# ALU.net
KiCad netlist of a schematic drawn in EAGLE
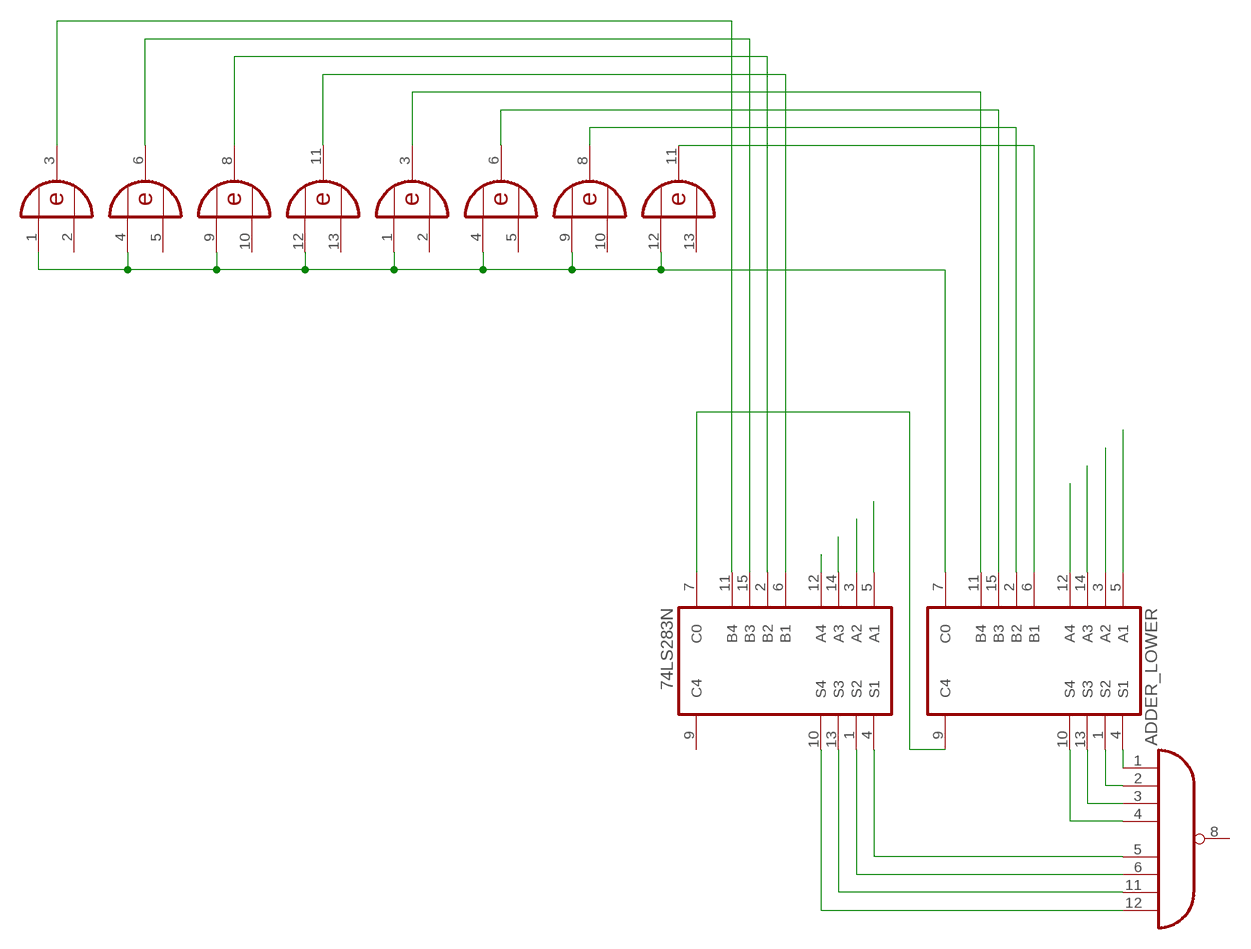
[diagram p0: schematic, sheet 1]

(export (version "E")
  (design (tool "Eeschema 10.0.6"))
  (components
    (comp (ref "ADDER_LOWER")
      (value "74LS283N")
      (footprint "eagle-import:DIL16")
      (libsource (lib "eagle-import") (part "74283NLS"))
    )
    (comp (ref "ADDER_UPPER")
      (value "74LS283N")
      (footprint "eagle-import:DIL16")
      (libsource (lib "eagle-import") (part "74283NLS"))
    )
    (comp (ref "AND_GATE1")
      (value "74LS30N")
      (footprint "eagle-import:DIL14")
      (libsource (lib "eagle-import") (part "7430NLS"))
    )
    (comp (ref "SUBTRACT_INVERTER_LOWER")
      (value "74LS86N")
      (footprint "eagle-import:DIL14")
      (libsource (lib "eagle-import") (part "7486NLS"))
    )
    (comp (ref "SUBTRACT_INVERTER_UPPER")
      (value "74LS86N")
      (footprint "eagle-import:DIL14")
      (libsource (lib "eagle-import") (part "7486NLS"))
    )
  )
  (nets
    (net (code "1") (name "Net-(ADDER_LOWERA-B1)") (class "Default")
      (node (ref "ADDER_LOWER") (pin "6") (pinfunction "B1_6") (pintype "input"))
      (node (ref "SUBTRACT_INVERTER_LOWER") (pin "11") (pinfunction "O_11") (pintype "output"))
    )
    (net (code "2") (name "Net-(ADDER_LOWERA-B2)") (class "Default")
      (node (ref "ADDER_LOWER") (pin "2") (pinfunction "B2_2") (pintype "input"))
      (node (ref "SUBTRACT_INVERTER_LOWER") (pin "8") (pinfunction "O_8") (pintype "output"))
    )
    (net (code "3") (name "Net-(ADDER_LOWERA-B3)") (class "Default")
      (node (ref "ADDER_LOWER") (pin "15") (pinfunction "B3_15") (pintype "input"))
      (node (ref "SUBTRACT_INVERTER_LOWER") (pin "6") (pinfunction "O_6") (pintype "output"))
    )
    (net (code "4") (name "Net-(ADDER_LOWERA-B4)") (class "Default")
      (node (ref "ADDER_LOWER") (pin "11") (pinfunction "B4_11") (pintype "input"))
      (node (ref "SUBTRACT_INVERTER_LOWER") (pin "3") (pinfunction "O_3") (pintype "output"))
    )
    (net (code "5") (name "Net-(ADDER_LOWERA-C0)") (class "Default")
      (node (ref "ADDER_LOWER") (pin "7") (pinfunction "C0_7") (pintype "input"))
      (node (ref "SUBTRACT_INVERTER_LOWER") (pin "1") (pinfunction "I0_1") (pintype "input"))
      (node (ref "SUBTRACT_INVERTER_LOWER") (pin "12") (pinfunction "I0_12") (pintype "input"))
      (node (ref "SUBTRACT_INVERTER_LOWER") (pin "4") (pinfunction "I0_4") (pintype "input"))
      (node (ref "SUBTRACT_INVERTER_LOWER") (pin "9") (pinfunction "I0_9") (pintype "input"))
      (node (ref "SUBTRACT_INVERTER_UPPER") (pin "1") (pinfunction "I0_1") (pintype "input"))
      (node (ref "SUBTRACT_INVERTER_UPPER") (pin "12") (pinfunction "I0_12") (pintype "input"))
      (node (ref "SUBTRACT_INVERTER_UPPER") (pin "4") (pinfunction "I0_4") (pintype "input"))
      (node (ref "SUBTRACT_INVERTER_UPPER") (pin "9") (pinfunction "I0_9") (pintype "input"))
    )
    (net (code "6") (name "Net-(ADDER_LOWERA-C4)") (class "Default")
      (node (ref "ADDER_LOWER") (pin "9") (pinfunction "C4_9") (pintype "output"))
      (node (ref "ADDER_UPPER") (pin "7") (pinfunction "C0_7") (pintype "input"))
    )
    (net (code "7") (name "Net-(ADDER_LOWERA-S1)") (class "Default")
      (node (ref "ADDER_LOWER") (pin "4") (pinfunction "S1_4") (pintype "output"))
      (node (ref "AND_GATE1") (pin "1") (pinfunction "I0_1") (pintype "input"))
    )
    (net (code "8") (name "Net-(ADDER_LOWERA-S2)") (class "Default")
      (node (ref "ADDER_LOWER") (pin "1") (pinfunction "S2_1") (pintype "output"))
      (node (ref "AND_GATE1") (pin "2") (pinfunction "I1_2") (pintype "input"))
    )
    (net (code "9") (name "Net-(ADDER_LOWERA-S3)") (class "Default")
      (node (ref "ADDER_LOWER") (pin "13") (pinfunction "S3_13") (pintype "output"))
      (node (ref "AND_GATE1") (pin "3") (pinfunction "I2_3") (pintype "input"))
    )
    (net (code "10") (name "Net-(ADDER_LOWERA-S4)") (class "Default")
      (node (ref "ADDER_LOWER") (pin "10") (pinfunction "S4_10") (pintype "output"))
      (node (ref "AND_GATE1") (pin "4") (pinfunction "I3_4") (pintype "input"))
    )
    (net (code "11") (name "Net-(ADDER_UPPERA-B1)") (class "Default")
      (node (ref "ADDER_UPPER") (pin "6") (pinfunction "B1_6") (pintype "input"))
      (node (ref "SUBTRACT_INVERTER_UPPER") (pin "11") (pinfunction "O_11") (pintype "output"))
    )
    (net (code "12") (name "Net-(ADDER_UPPERA-B2)") (class "Default")
      (node (ref "ADDER_UPPER") (pin "2") (pinfunction "B2_2") (pintype "input"))
      (node (ref "SUBTRACT_INVERTER_UPPER") (pin "8") (pinfunction "O_8") (pintype "output"))
    )
    (net (code "13") (name "Net-(ADDER_UPPERA-B3)") (class "Default")
      (node (ref "ADDER_UPPER") (pin "15") (pinfunction "B3_15") (pintype "input"))
      (node (ref "SUBTRACT_INVERTER_UPPER") (pin "6") (pinfunction "O_6") (pintype "output"))
    )
    (net (code "14") (name "Net-(ADDER_UPPERA-B4)") (class "Default")
      (node (ref "ADDER_UPPER") (pin "11") (pinfunction "B4_11") (pintype "input"))
      (node (ref "SUBTRACT_INVERTER_UPPER") (pin "3") (pinfunction "O_3") (pintype "output"))
    )
    (net (code "15") (name "Net-(ADDER_UPPERA-S1)") (class "Default")
      (node (ref "ADDER_UPPER") (pin "4") (pinfunction "S1_4") (pintype "output"))
      (node (ref "AND_GATE1") (pin "5") (pinfunction "I4_5") (pintype "input"))
    )
    (net (code "16") (name "Net-(ADDER_UPPERA-S2)") (class "Default")
      (node (ref "ADDER_UPPER") (pin "1") (pinfunction "S2_1") (pintype "output"))
      (node (ref "AND_GATE1") (pin "6") (pinfunction "I5_6") (pintype "input"))
    )
    (net (code "17") (name "Net-(ADDER_UPPERA-S3)") (class "Default")
      (node (ref "ADDER_UPPER") (pin "13") (pinfunction "S3_13") (pintype "output"))
      (node (ref "AND_GATE1") (pin "11") (pinfunction "I6_11") (pintype "input"))
    )
    (net (code "18") (name "Net-(ADDER_UPPERA-S4)") (class "Default")
      (node (ref "ADDER_UPPER") (pin "10") (pinfunction "S4_10") (pintype "output"))
      (node (ref "AND_GATE1") (pin "12") (pinfunction "I7_12") (pintype "input"))
    )
    (net (code "19") (name "unconnected-(ADDER_LOWERA-A1-Pad5)") (class "Default")
      (node (ref "ADDER_LOWER") (pin "5") (pinfunction "A1_5") (pintype "input"))
    )
    (net (code "20") (name "unconnected-(ADDER_LOWERA-A2-Pad3)") (class "Default")
      (node (ref "ADDER_LOWER") (pin "3") (pinfunction "A2_3") (pintype "input"))
    )
    (net (code "21") (name "unconnected-(ADDER_LOWERA-A3-Pad14)") (class "Default")
      (node (ref "ADDER_LOWER") (pin "14") (pinfunction "A3_14") (pintype "input"))
    )
    (net (code "22") (name "unconnected-(ADDER_LOWERA-A4-Pad12)") (class "Default")
      (node (ref "ADDER_LOWER") (pin "12") (pinfunction "A4_12") (pintype "input"))
    )
    (net (code "23") (name "unconnected-(ADDER_UPPERA-A1-Pad5)") (class "Default")
      (node (ref "ADDER_UPPER") (pin "5") (pinfunction "A1_5") (pintype "input"))
    )
    (net (code "24") (name "unconnected-(ADDER_UPPERA-A2-Pad3)") (class "Default")
      (node (ref "ADDER_UPPER") (pin "3") (pinfunction "A2_3") (pintype "input"))
    )
    (net (code "25") (name "unconnected-(ADDER_UPPERA-A3-Pad14)") (class "Default")
      (node (ref "ADDER_UPPER") (pin "14") (pinfunction "A3_14") (pintype "input"))
    )
    (net (code "26") (name "unconnected-(ADDER_UPPERA-A4-Pad12)") (class "Default")
      (node (ref "ADDER_UPPER") (pin "12") (pinfunction "A4_12") (pintype "input"))
    )
    (net (code "27") (name "unconnected-(ADDER_UPPERA-C4-Pad9)") (class "Default")
      (node (ref "ADDER_UPPER") (pin "9") (pinfunction "C4_9") (pintype "output"))
    )
    (net (code "28") (name "unconnected-(AND_GATE1A-O-Pad8)") (class "Default")
      (node (ref "AND_GATE1") (pin "8") (pinfunction "O_8") (pintype "output"))
    )
    (net (code "29") (name "unconnected-(SUBTRACT_INVERTER_LOWERA-I1-Pad2)") (class "Default")
      (node (ref "SUBTRACT_INVERTER_LOWER") (pin "2") (pinfunction "I1_2") (pintype "input"))
    )
    (net (code "30") (name "unconnected-(SUBTRACT_INVERTER_LOWERB-I1-Pad5)") (class "Default")
      (node (ref "SUBTRACT_INVERTER_LOWER") (pin "5") (pinfunction "I1_5") (pintype "input"))
    )
    (net (code "31") (name "unconnected-(SUBTRACT_INVERTER_LOWERC-I1-Pad10)") (class "Default")
      (node (ref "SUBTRACT_INVERTER_LOWER") (pin "10") (pinfunction "I1_10") (pintype "input"))
    )
    (net (code "32") (name "unconnected-(SUBTRACT_INVERTER_LOWERD-I1-Pad13)") (class "Default")
      (node (ref "SUBTRACT_INVERTER_LOWER") (pin "13") (pinfunction "I1_13") (pintype "input"))
    )
    (net (code "33") (name "unconnected-(SUBTRACT_INVERTER_UPPERA-I1-Pad2)") (class "Default")
      (node (ref "SUBTRACT_INVERTER_UPPER") (pin "2") (pinfunction "I1_2") (pintype "input"))
    )
    (net (code "34") (name "unconnected-(SUBTRACT_INVERTER_UPPERB-I1-Pad5)") (class "Default")
      (node (ref "SUBTRACT_INVERTER_UPPER") (pin "5") (pinfunction "I1_5") (pintype "input"))
    )
    (net (code "35") (name "unconnected-(SUBTRACT_INVERTER_UPPERC-I1-Pad10)") (class "Default")
      (node (ref "SUBTRACT_INVERTER_UPPER") (pin "10") (pinfunction "I1_10") (pintype "input"))
    )
    (net (code "36") (name "unconnected-(SUBTRACT_INVERTER_UPPERD-I1-Pad13)") (class "Default")
      (node (ref "SUBTRACT_INVERTER_UPPER") (pin "13") (pinfunction "I1_13") (pintype "input"))
    )
  )
)
